# Audio.net
KiCad netlist of a schematic drawn in Altium Designer
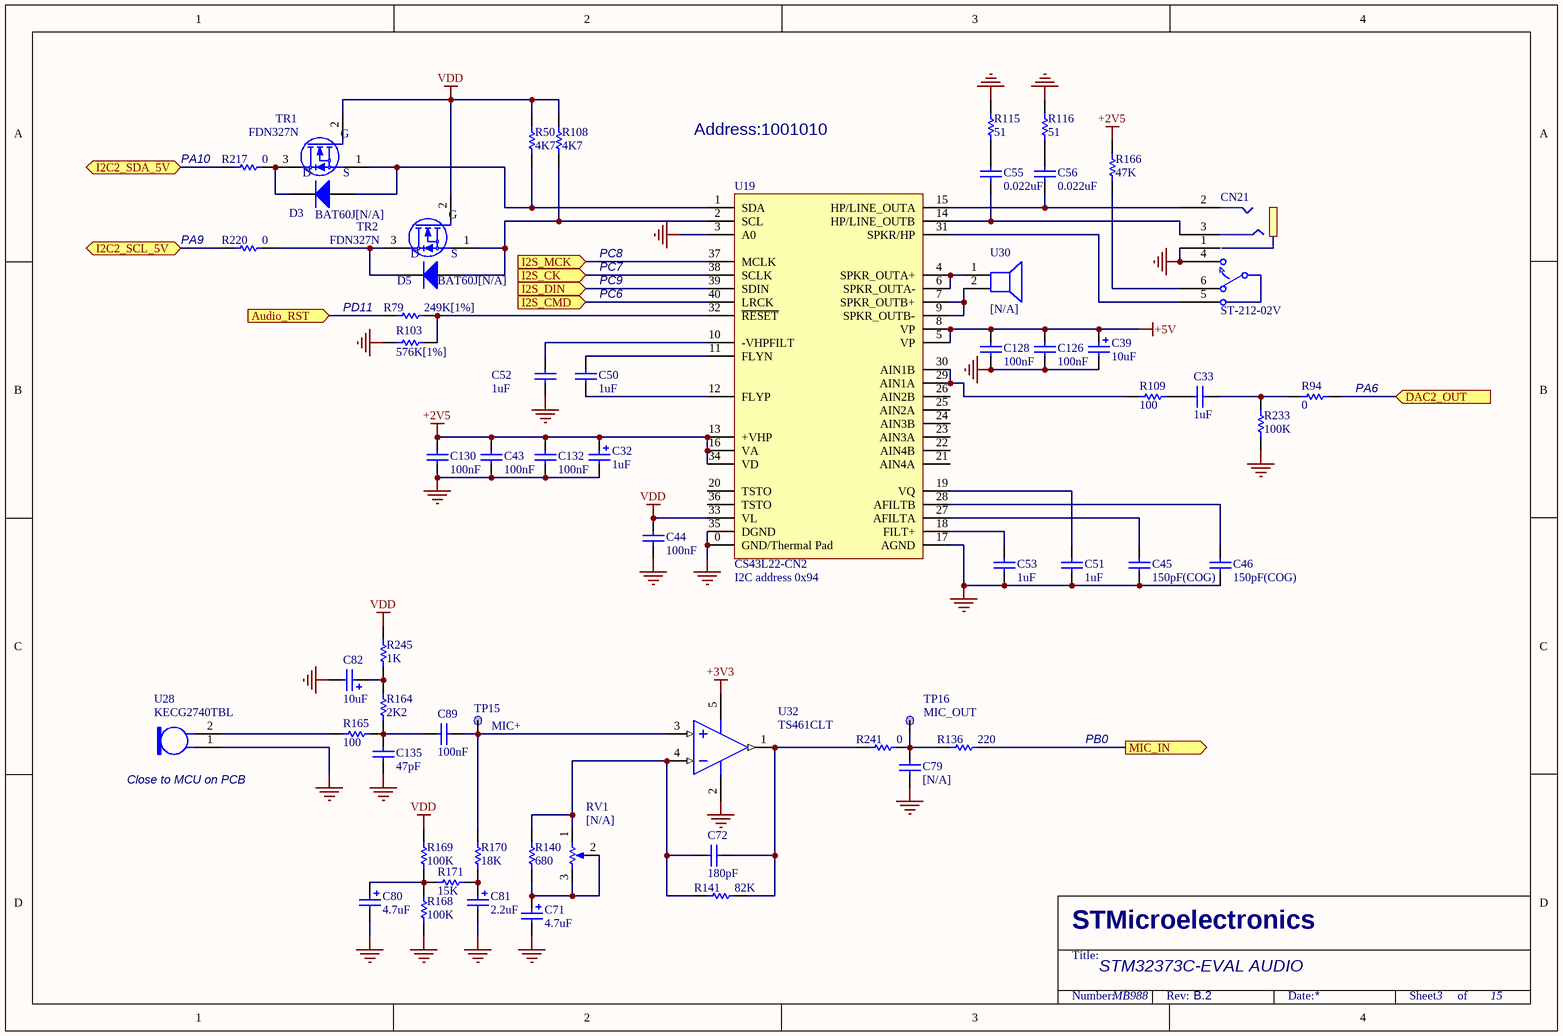
[diagram p0: Audio.SchDoc]

(export (version "E")
  (design (tool "Eeschema 10.0.6"))
  (components
    (comp (ref "C32")
      (value "1uF")
      (footprint "TAN-A")
      (description "Polarized Capacitor (Radial)")
      (fields (field (name "PUBLISHER") "Altium Limited"))
      (libsource (lib "Miscellaneous Devices") (part "Cap Pol1"))
    )
    (comp (ref "C33")
      (value "1uF")
      (footprint "0603C")
      (description "Capacitor")
      (fields (field (name "PUBLISHER") "Altium Limited"))
      (libsource (lib "Miscellaneous Devices") (part "CAP"))
    )
    (comp (ref "C39")
      (value "10uF")
      (footprint "TAN-A")
      (description "Polarized Capacitor (Radial)")
      (fields (field (name "PUBLISHER") "Altium Limited"))
      (libsource (lib "Miscellaneous Devices") (part "Cap Pol1"))
    )
    (comp (ref "C43")
      (value "100nF")
      (footprint "0603C")
      (description "Capacitor")
      (fields (field (name "PUBLISHER") "Altium Limited"))
      (libsource (lib "Miscellaneous Devices") (part "Cap"))
    )
    (comp (ref "C44")
      (value "100nF")
      (footprint "0603C")
      (description "Capacitor")
      (fields (field (name "PUBLISHER") "Altium Limited"))
      (libsource (lib "Miscellaneous Devices") (part "Cap"))
    )
    (comp (ref "C45")
      (value "150pF(COG)")
      (footprint "0603C")
      (description "Capacitor")
      (fields (field (name "PUBLISHER") "Altium Limited"))
      (libsource (lib "Miscellaneous Devices") (part "CAP"))
    )
    (comp (ref "C46")
      (value "150pF(COG)")
      (footprint "0603C")
      (description "Capacitor")
      (fields (field (name "PUBLISHER") "Altium Limited"))
      (libsource (lib "Miscellaneous Devices") (part "CAP"))
    )
    (comp (ref "C50")
      (value "1uF")
      (footprint "0603C")
      (description "Capacitor")
      (fields (field (name "PUBLISHER") "Altium Limited"))
      (libsource (lib "Miscellaneous Devices") (part "CAP"))
    )
    (comp (ref "C51")
      (value "1uF")
      (footprint "0603C")
      (description "Capacitor")
      (fields (field (name "PUBLISHER") "Altium Limited"))
      (libsource (lib "Miscellaneous Devices") (part "CAP"))
    )
    (comp (ref "C52")
      (value "1uF")
      (footprint "0603C")
      (description "Capacitor")
      (fields (field (name "PUBLISHER") "Altium Limited"))
      (libsource (lib "Miscellaneous Devices") (part "CAP"))
    )
    (comp (ref "C53")
      (value "1uF")
      (footprint "0603C")
      (description "Capacitor")
      (fields (field (name "PUBLISHER") "Altium Limited"))
      (libsource (lib "Miscellaneous Devices") (part "CAP"))
    )
    (comp (ref "C55")
      (value "0.022uF")
      (footprint "0603C")
      (description "Capacitor")
      (fields (field (name "PUBLISHER") "Altium Limited"))
      (libsource (lib "Miscellaneous Devices") (part "CAP"))
    )
    (comp (ref "C56")
      (value "0.022uF")
      (footprint "0603C")
      (description "Capacitor")
      (fields (field (name "PUBLISHER") "Altium Limited"))
      (libsource (lib "Miscellaneous Devices") (part "CAP"))
    )
    (comp (ref "C71")
      (value "4.7uF")
      (footprint "TAN-A")
      (description "Polarized Capacitor (Radial)")
      (fields (field (name "PUBLISHER") "Altium Limited"))
      (libsource (lib "*") (part "Cap Pol1"))
    )
    (comp (ref "C72")
      (value "180pF")
      (footprint "0603C")
      (description "Capacitor")
      (fields (field (name "PUBLISHER") "Altium Limited"))
      (libsource (lib "Miscellaneous Devices") (part "CAP"))
    )
    (comp (ref "C79")
      (value "[N/A]")
      (footprint "0603C")
      (description "Capacitor")
      (fields (field (name "PUBLISHER") "Altium Limited"))
      (libsource (lib "Miscellaneous Devices") (part "CAP"))
    )
    (comp (ref "C80")
      (value "4.7uF")
      (footprint "TAN-A")
      (description "Polarized Capacitor (Radial)")
      (fields (field (name "PUBLISHER") "Altium Limited"))
      (libsource (lib "*") (part "Cap Pol1"))
    )
    (comp (ref "C81")
      (value "2.2uF")
      (footprint "0805C")
      (description "Polarized Capacitor (Radial)")
      (fields (field (name "PUBLISHER") "Altium Limited"))
      (libsource (lib "*") (part "Cap Pol1"))
    )
    (comp (ref "C82")
      (value "10uF")
      (footprint "TAN-A")
      (description "Polarized Capacitor (Radial)")
      (fields (field (name "PUBLISHER") "Altium Limited"))
      (libsource (lib "*") (part "Cap Pol1"))
    )
    (comp (ref "C89")
      (value "100nF")
      (footprint "0603C")
      (description "Capacitor")
      (fields (field (name "PUBLISHER") "Altium Limited"))
      (libsource (lib "Miscellaneous Devices") (part "CAP"))
    )
    (comp (ref "C126")
      (value "100nF")
      (footprint "0603C")
      (description "Capacitor")
      (fields (field (name "PUBLISHER") "Altium Limited"))
      (libsource (lib "Miscellaneous Devices") (part "Cap"))
    )
    (comp (ref "C128")
      (value "100nF")
      (footprint "0603C")
      (description "Capacitor")
      (fields (field (name "PUBLISHER") "Altium Limited"))
      (libsource (lib "Miscellaneous Devices") (part "Cap"))
    )
    (comp (ref "C130")
      (value "100nF")
      (footprint "0603C")
      (description "Capacitor")
      (fields (field (name "PUBLISHER") "Altium Limited"))
      (libsource (lib "Miscellaneous Devices") (part "Cap"))
    )
    (comp (ref "C132")
      (value "100nF")
      (footprint "0603C")
      (description "Capacitor")
      (fields (field (name "PUBLISHER") "Altium Limited"))
      (libsource (lib "Miscellaneous Devices") (part "Cap"))
    )
    (comp (ref "C135")
      (value "47pF")
      (footprint "0603C")
      (description "Capacitor")
      (fields (field (name "PUBLISHER") "Altium Limited"))
      (libsource (lib "Miscellaneous Devices") (part "CAP"))
    )
    (comp (ref "CN21")
      (value "ST-212-02V")
      (footprint "ST-212-02V")
      (libsource (lib "MB784") (part "ST-212-02V"))
    )
    (comp (ref "D3")
      (value "BAT60J[N/A]")
      (footprint "SOD-323")
      (description "Default Diode")
      (fields (field (name "PUBLISHER") "Altium Limited"))
      (libsource (lib "Miscellaneous Devices") (part "Diode"))
    )
    (comp (ref "D5")
      (value "BAT60J[N/A]")
      (footprint "SOD-323")
      (description "Default Diode")
      (fields (field (name "PUBLISHER") "Altium Limited"))
      (libsource (lib "Miscellaneous Devices") (part "Diode"))
    )
    (comp (ref "R50")
      (value "4K7")
      (footprint "0603R")
      (description "Resistor")
      (fields (field (name "PUBLISHER") "Altium Limited"))
      (libsource (lib "Miscellaneous Devices") (part "Res1"))
    )
    (comp (ref "R79")
      (value "249K[1%]")
      (footprint "0603R")
      (description "Resistor")
      (fields (field (name "PUBLISHER") "Altium Limited"))
      (libsource (lib "Miscellaneous Devices") (part "res1"))
    )
    (comp (ref "R94")
      (value "0")
      (footprint "0603R")
      (description "Resistor")
      (fields (field (name "PUBLISHER") "Altium Limited"))
      (libsource (lib "Miscellaneous Devices") (part "res1"))
    )
    (comp (ref "R103")
      (value "576K[1%]")
      (footprint "0603R")
      (description "Resistor")
      (fields (field (name "PUBLISHER") "Altium Limited"))
      (libsource (lib "Miscellaneous Devices") (part "res1"))
    )
    (comp (ref "R108")
      (value "4K7")
      (footprint "0603R")
      (description "Resistor")
      (fields (field (name "PUBLISHER") "Altium Limited"))
      (libsource (lib "Miscellaneous Devices") (part "Res1"))
    )
    (comp (ref "R109")
      (value "100")
      (footprint "0603R")
      (description "Resistor")
      (fields (field (name "PUBLISHER") "Altium Limited"))
      (libsource (lib "Miscellaneous Devices") (part "res1"))
    )
    (comp (ref "R115")
      (value "51")
      (footprint "0603R")
      (description "Resistor")
      (fields (field (name "PUBLISHER") "Altium Limited"))
      (libsource (lib "Miscellaneous Devices") (part "res1"))
    )
    (comp (ref "R116")
      (value "51")
      (footprint "0603R")
      (description "Resistor")
      (fields (field (name "PUBLISHER") "Altium Limited"))
      (libsource (lib "Miscellaneous Devices") (part "res1"))
    )
    (comp (ref "R136")
      (value "220")
      (footprint "0603R")
      (description "Resistor")
      (fields (field (name "PUBLISHER") "Altium Limited"))
      (libsource (lib "Miscellaneous Devices") (part "Res1"))
    )
    (comp (ref "R140")
      (value "680")
      (footprint "0603R")
      (description "Resistor")
      (fields (field (name "PUBLISHER") "Altium Limited"))
      (libsource (lib "Miscellaneous Devices") (part "Res1"))
    )
    (comp (ref "R141")
      (value "82K")
      (footprint "0603R")
      (description "Resistor")
      (fields (field (name "PUBLISHER") "Altium Limited"))
      (libsource (lib "Miscellaneous Devices") (part "Res1"))
    )
    (comp (ref "R164")
      (value "2K2")
      (footprint "0603R")
      (description "Resistor")
      (fields (field (name "PUBLISHER") "Altium Limited"))
      (libsource (lib "Miscellaneous Devices") (part "Res1"))
    )
    (comp (ref "R165")
      (value "100")
      (footprint "0603R")
      (description "Resistor")
      (fields (field (name "PUBLISHER") "Altium Limited"))
      (libsource (lib "Miscellaneous Devices") (part "Res1"))
    )
    (comp (ref "R166")
      (value "47K")
      (footprint "0603R")
      (description "Resistor")
      (fields (field (name "PUBLISHER") "Altium Limited"))
      (libsource (lib "Miscellaneous Devices") (part "res1"))
    )
    (comp (ref "R168")
      (value "100K")
      (footprint "0603R")
      (description "Resistor")
      (fields (field (name "PUBLISHER") "Altium Limited"))
      (libsource (lib "Miscellaneous Devices") (part "Res1"))
    )
    (comp (ref "R169")
      (value "100K")
      (footprint "0603R")
      (description "Resistor")
      (fields (field (name "PUBLISHER") "Altium Limited"))
      (libsource (lib "Miscellaneous Devices") (part "Res1"))
    )
    (comp (ref "R170")
      (value "18K")
      (footprint "0603R")
      (description "Resistor")
      (fields (field (name "PUBLISHER") "Altium Limited"))
      (libsource (lib "Miscellaneous Devices") (part "Res1"))
    )
    (comp (ref "R171")
      (value "15K")
      (footprint "0603R")
      (description "Resistor")
      (fields (field (name "PUBLISHER") "Altium Limited"))
      (libsource (lib "Miscellaneous Devices") (part "Res1"))
    )
    (comp (ref "R217")
      (value "0")
      (footprint "0603R")
      (description "Resistor")
      (fields (field (name "PUBLISHER") "Altium Limited"))
      (libsource (lib "Miscellaneous Devices") (part "Res1"))
    )
    (comp (ref "R220")
      (value "0")
      (footprint "0603R")
      (description "Resistor")
      (fields (field (name "PUBLISHER") "Altium Limited"))
      (libsource (lib "Miscellaneous Devices") (part "Res1"))
    )
    (comp (ref "R233")
      (value "100K")
      (footprint "0603R")
      (description "Resistor")
      (fields (field (name "PUBLISHER") "Altium Limited"))
      (libsource (lib "Miscellaneous Devices") (part "res1"))
    )
    (comp (ref "R241")
      (value "0")
      (footprint "0603R")
      (description "Resistor")
      (fields (field (name "PUBLISHER") "Altium Limited"))
      (libsource (lib "Miscellaneous Devices") (part "Res1"))
    )
    (comp (ref "R245")
      (value "1K")
      (footprint "0603R")
      (description "Resistor")
      (fields (field (name "PUBLISHER") "Altium Limited"))
      (libsource (lib "Miscellaneous Devices") (part "Res1"))
    )
    (comp (ref "RV1") (value "[N/A]") (footprint "3314-J") (libsource (lib "STR910_SCHLIB") (part "RV")))
    (comp (ref "TP15") (value "MIC+") (footprint "TP") (libsource (lib "*") (part "TP")))
    (comp (ref "TP16") (value "MIC_OUT") (footprint "TP") (libsource (lib "*") (part "TP")))
    (comp (ref "TR1") (value "FDN327N") (footprint "SOT-23") (libsource (lib "MB525") (part "2N7000")))
    (comp (ref "TR2") (value "FDN327N") (footprint "SOT-23") (libsource (lib "MB525") (part "2N7000")))
    (comp (ref "U19")
      (value "CS43L22-CN2")
      (footprint "QFN40(6*6)")
      (libsource (lib "MB784") (part "CS43L22"))
    )
    (comp (ref "U28")
      (value "KECG2740TBL")
      (footprint "KEC2740")
      (description "Microphone")
      (fields (field (name "PUBLISHER") "Altium Limited"))
      (libsource (lib "Miscellaneous Devices") (part "Mic2"))
    )
    (comp (ref "U30")
      (value "[N/A]")
      (footprint "KS1708")
      (description "Loudspeaker")
      (fields (field (name "PUBLISHER") "Altium Limited"))
      (libsource (lib "Miscellaneous Devices") (part "Speaker"))
    )
    (comp (ref "U32")
      (value "TS461CLT")
      (footprint "SOT-23-5L")
      (libsource (lib "MB819_1") (part "TS461CLT"))
    )
  )
  (nets
    (net (code "1") (name "+2V5") (class "Default")
      (node (ref "C130") (pin "1") (pinfunction "1_1") (pintype "passive"))
      (node (ref "C132") (pin "1") (pinfunction "1_1") (pintype "passive"))
      (node (ref "C32") (pin "1") (pinfunction "1_1") (pintype "passive"))
      (node (ref "C43") (pin "1") (pinfunction "1_1") (pintype "passive"))
      (node (ref "R166") (pin "1") (pinfunction "1_1") (pintype "passive"))
      (node (ref "U19") (pin "13") (pinfunction "+VHP_13") (pintype "passive"))
      (node (ref "U19") (pin "16") (pinfunction "VA_16") (pintype "passive"))
      (node (ref "U19") (pin "34") (pinfunction "VD_34") (pintype "passive"))
    )
    (net (code "2") (name "+3V3") (class "Default")
      (node (ref "U32") (pin "5") (pinfunction "VCC_5") (pintype "power_in"))
    )
    (net (code "3") (name "+5V") (class "Default")
      (node (ref "C126") (pin "1") (pinfunction "1_1") (pintype "passive"))
      (node (ref "C128") (pin "1") (pinfunction "1_1") (pintype "passive"))
      (node (ref "C39") (pin "1") (pinfunction "1_1") (pintype "passive"))
      (node (ref "U19") (pin "5") (pinfunction "VP_5") (pintype "passive"))
      (node (ref "U19") (pin "8") (pinfunction "VP_8") (pintype "passive"))
    )
    (net (code "4") (name "/Audio_RST") (class "Default")
      (node (ref "R79") (pin "2") (pinfunction "2_2") (pintype "passive"))
    )
    (net (code "5") (name "/DAC2_OUT") (class "Default")
      (node (ref "R94") (pin "2") (pinfunction "2_2") (pintype "passive"))
    )
    (net (code "6") (name "/I2C2_SCL_5V") (class "Default")
      (node (ref "R220") (pin "1") (pinfunction "1_1") (pintype "passive"))
    )
    (net (code "7") (name "/I2C2_SDA_5V") (class "Default")
      (node (ref "R217") (pin "1") (pinfunction "1_1") (pintype "passive"))
    )
    (net (code "8") (name "/I2S_CK") (class "Default")
      (node (ref "U19") (pin "38") (pinfunction "SCLK_38") (pintype "passive"))
    )
    (net (code "9") (name "/I2S_CMD") (class "Default")
      (node (ref "U19") (pin "40") (pinfunction "LRCK_40") (pintype "passive"))
    )
    (net (code "10") (name "/I2S_DIN") (class "Default")
      (node (ref "U19") (pin "39") (pinfunction "SDIN_39") (pintype "passive"))
    )
    (net (code "11") (name "/I2S_MCK") (class "Default")
      (node (ref "U19") (pin "37") (pinfunction "MCLK_37") (pintype "passive"))
    )
    (net (code "12") (name "/MIC_IN") (class "Default")
      (node (ref "R136") (pin "1") (pinfunction "1_1") (pintype "passive"))
    )
    (net (code "13") (name "GND") (class "Default")
      (node (ref "C126") (pin "2") (pinfunction "2_2") (pintype "passive"))
      (node (ref "C128") (pin "2") (pinfunction "2_2") (pintype "passive"))
      (node (ref "C130") (pin "2") (pinfunction "2_2") (pintype "passive"))
      (node (ref "C132") (pin "2") (pinfunction "2_2") (pintype "passive"))
      (node (ref "C135") (pin "2") (pinfunction "2_2") (pintype "passive"))
      (node (ref "C32") (pin "2") (pinfunction "2_2") (pintype "passive"))
      (node (ref "C39") (pin "2") (pinfunction "2_2") (pintype "passive"))
      (node (ref "C43") (pin "2") (pinfunction "2_2") (pintype "passive"))
      (node (ref "C44") (pin "2") (pinfunction "2_2") (pintype "passive"))
      (node (ref "C45") (pin "1") (pinfunction "1_1") (pintype "passive"))
      (node (ref "C46") (pin "1") (pinfunction "1_1") (pintype "passive"))
      (node (ref "C51") (pin "1") (pinfunction "1_1") (pintype "passive"))
      (node (ref "C52") (pin "2") (pinfunction "2_2") (pintype "passive"))
      (node (ref "C53") (pin "1") (pinfunction "1_1") (pintype "passive"))
      (node (ref "C71") (pin "2") (pinfunction "2_2") (pintype "passive"))
      (node (ref "C79") (pin "2") (pinfunction "2_2") (pintype "passive"))
      (node (ref "C80") (pin "2") (pinfunction "2_2") (pintype "passive"))
      (node (ref "C81") (pin "2") (pinfunction "2_2") (pintype "passive"))
      (node (ref "C82") (pin "2") (pinfunction "2_2") (pintype "passive"))
      (node (ref "CN21") (pin "1") (pintype "passive"))
      (node (ref "CN21") (pin "4") (pintype "passive"))
      (node (ref "R103") (pin "1") (pinfunction "1_1") (pintype "passive"))
      (node (ref "R115") (pin "1") (pinfunction "1_1") (pintype "passive"))
      (node (ref "R116") (pin "1") (pinfunction "1_1") (pintype "passive"))
      (node (ref "R168") (pin "2") (pinfunction "2_2") (pintype "passive"))
      (node (ref "R233") (pin "2") (pinfunction "2_2") (pintype "passive"))
      (node (ref "U19") (pin "0") (pinfunction "GND/Thermal_Pad_0") (pintype "passive"))
      (node (ref "U19") (pin "17") (pinfunction "AGND_17") (pintype "passive"))
      (node (ref "U19") (pin "3") (pinfunction "A0_3") (pintype "passive"))
      (node (ref "U19") (pin "35") (pinfunction "DGND_35") (pintype "passive"))
      (node (ref "U28") (pin "1") (pinfunction "1_1") (pintype "passive"))
      (node (ref "U32") (pin "2") (pinfunction "VDD_2") (pintype "power_in"))
    )
    (net (code "14") (name "Net-(C33-Pad1)") (class "Default")
      (node (ref "C33") (pin "1") (pinfunction "1_1") (pintype "passive"))
      (node (ref "R109") (pin "1") (pinfunction "1_1") (pintype "passive"))
    )
    (net (code "15") (name "Net-(C33-Pad2)") (class "Default")
      (node (ref "C33") (pin "2") (pinfunction "2_2") (pintype "passive"))
      (node (ref "R233") (pin "1") (pinfunction "1_1") (pintype "passive"))
      (node (ref "R94") (pin "1") (pinfunction "1_1") (pintype "passive"))
    )
    (net (code "16") (name "Net-(C55-Pad1)") (class "Default")
      (node (ref "C55") (pin "1") (pinfunction "1_1") (pintype "passive"))
      (node (ref "R115") (pin "2") (pinfunction "2_2") (pintype "passive"))
    )
    (net (code "17") (name "Net-(C56-Pad1)") (class "Default")
      (node (ref "C56") (pin "1") (pinfunction "1_1") (pintype "passive"))
      (node (ref "R116") (pin "2") (pinfunction "2_2") (pintype "passive"))
    )
    (net (code "18") (name "Net-(C79-Pad1)") (class "Default")
      (node (ref "C79") (pin "1") (pinfunction "1_1") (pintype "passive"))
      (node (ref "R136") (pin "2") (pinfunction "2_2") (pintype "passive"))
      (node (ref "R241") (pin "1") (pinfunction "1_1") (pintype "passive"))
      (node (ref "TP16") (pin "1") (pinfunction "1_1") (pintype "passive"))
    )
    (net (code "19") (name "Net-(C80-Pad1)") (class "Default")
      (node (ref "C80") (pin "1") (pinfunction "1_1") (pintype "passive"))
      (node (ref "R168") (pin "1") (pinfunction "1_1") (pintype "passive"))
      (node (ref "R169") (pin "2") (pinfunction "2_2") (pintype "passive"))
      (node (ref "R171") (pin "1") (pinfunction "1_1") (pintype "passive"))
    )
    (net (code "20") (name "Net-(C81-Pad1)") (class "Default")
      (node (ref "C81") (pin "1") (pinfunction "1_1") (pintype "passive"))
      (node (ref "R170") (pin "1") (pinfunction "1_1") (pintype "passive"))
      (node (ref "R171") (pin "2") (pinfunction "2_2") (pintype "passive"))
    )
    (net (code "21") (name "Net-(C82-Pad1)") (class "Default")
      (node (ref "C82") (pin "1") (pinfunction "1_1") (pintype "passive"))
      (node (ref "R164") (pin "2") (pinfunction "2_2") (pintype "passive"))
      (node (ref "R245") (pin "1") (pinfunction "1_1") (pintype "passive"))
    )
    (net (code "22") (name "Net-(C135-Pad1)") (class "Default")
      (node (ref "C135") (pin "1") (pinfunction "1_1") (pintype "passive"))
      (node (ref "C89") (pin "1") (pinfunction "1_1") (pintype "passive"))
      (node (ref "R164") (pin "1") (pinfunction "1_1") (pintype "passive"))
      (node (ref "R165") (pin "1") (pinfunction "1_1") (pintype "passive"))
    )
    (net (code "23") (name "Net-(CN21-Pad6)") (class "Default")
      (node (ref "CN21") (pin "6") (pintype "passive"))
      (node (ref "R166") (pin "2") (pinfunction "2_2") (pintype "passive"))
    )
    (net (code "24") (name "Net-(D3-A)") (class "Default")
      (node (ref "D3") (pin "1") (pinfunction "A_1") (pintype "passive"))
      (node (ref "R50") (pin "1") (pinfunction "1_1") (pintype "passive"))
      (node (ref "TR1") (pin "1") (pinfunction "S_1") (pintype "passive"))
      (node (ref "U19") (pin "1") (pinfunction "SDA_1") (pintype "passive"))
    )
    (net (code "25") (name "Net-(D3-K)") (class "Default")
      (node (ref "D3") (pin "2") (pinfunction "K_2") (pintype "passive"))
      (node (ref "R217") (pin "2") (pinfunction "2_2") (pintype "passive"))
      (node (ref "TR1") (pin "3") (pinfunction "D_3") (pintype "passive"))
    )
    (net (code "26") (name "Net-(D5-A)") (class "Default")
      (node (ref "D5") (pin "1") (pinfunction "A_1") (pintype "passive"))
      (node (ref "R108") (pin "1") (pinfunction "1_1") (pintype "passive"))
      (node (ref "TR2") (pin "1") (pinfunction "S_1") (pintype "passive"))
      (node (ref "U19") (pin "2") (pinfunction "SCL_2") (pintype "passive"))
    )
    (net (code "27") (name "Net-(D5-K)") (class "Default")
      (node (ref "D5") (pin "2") (pinfunction "K_2") (pintype "passive"))
      (node (ref "R220") (pin "2") (pinfunction "2_2") (pintype "passive"))
      (node (ref "TR2") (pin "3") (pinfunction "D_3") (pintype "passive"))
    )
    (net (code "28") (name "Net-(R165-Pad2)") (class "Default")
      (node (ref "R165") (pin "2") (pinfunction "2_2") (pintype "passive"))
      (node (ref "U28") (pin "2") (pinfunction "2_2") (pintype "passive"))
    )
    (net (code "29") (name "Net-(RV1-BOT)") (class "Default")
      (node (ref "C72") (pin "1") (pinfunction "1_1") (pintype "passive"))
      (node (ref "R140") (pin "1") (pinfunction "1_1") (pintype "passive"))
      (node (ref "R141") (pin "2") (pinfunction "2_2") (pintype "passive"))
      (node (ref "RV1") (pin "1") (pinfunction "BOT_1") (pintype "passive"))
      (node (ref "U32") (pin "4") (pinfunction "IN-_4") (pintype "input"))
    )
    (net (code "30") (name "Net-(RV1-TAP)") (class "Default")
      (node (ref "C71") (pin "1") (pinfunction "1_1") (pintype "passive"))
      (node (ref "R140") (pin "2") (pinfunction "2_2") (pintype "passive"))
      (node (ref "RV1") (pin "2") (pinfunction "TAP_2") (pintype "passive"))
      (node (ref "RV1") (pin "3") (pinfunction "TOP_3") (pintype "passive"))
    )
    (net (code "31") (name "Net-(U19--VHPFILT)") (class "Default")
      (node (ref "C52") (pin "1") (pinfunction "1_1") (pintype "passive"))
      (node (ref "U19") (pin "10") (pinfunction "-VHPFILT_10") (pintype "passive"))
    )
    (net (code "32") (name "Net-(U19-AFILTA)") (class "Default")
      (node (ref "C45") (pin "2") (pinfunction "2_2") (pintype "passive"))
      (node (ref "U19") (pin "27") (pinfunction "AFILTA_27") (pintype "passive"))
    )
    (net (code "33") (name "Net-(U19-AFILTB)") (class "Default")
      (node (ref "C46") (pin "2") (pinfunction "2_2") (pintype "passive"))
      (node (ref "U19") (pin "28") (pinfunction "AFILTB_28") (pintype "passive"))
    )
    (net (code "34") (name "Net-(U19-AIN1A)") (class "Default")
      (node (ref "R109") (pin "2") (pinfunction "2_2") (pintype "passive"))
      (node (ref "U19") (pin "29") (pinfunction "AIN1A_29") (pintype "passive"))
      (node (ref "U19") (pin "30") (pinfunction "AIN1B_30") (pintype "passive"))
    )
    (net (code "35") (name "Net-(U19-FILT+)") (class "Default")
      (node (ref "C53") (pin "2") (pinfunction "2_2") (pintype "passive"))
      (node (ref "U19") (pin "18") (pinfunction "FILT+_18") (pintype "passive"))
    )
    (net (code "36") (name "Net-(U19-FLYN)") (class "Default")
      (node (ref "C50") (pin "2") (pinfunction "2_2") (pintype "passive"))
      (node (ref "U19") (pin "11") (pinfunction "FLYN_11") (pintype "passive"))
    )
    (net (code "37") (name "Net-(U19-FLYP)") (class "Default")
      (node (ref "C50") (pin "1") (pinfunction "1_1") (pintype "passive"))
      (node (ref "U19") (pin "12") (pinfunction "FLYP_12") (pintype "passive"))
    )
    (net (code "38") (name "Net-(U19-HP{slash}LINE_OUTA)") (class "Default")
      (node (ref "C56") (pin "2") (pinfunction "2_2") (pintype "passive"))
      (node (ref "CN21") (pin "2") (pintype "passive"))
      (node (ref "U19") (pin "15") (pinfunction "HP/LINE_OUTA_15") (pintype "passive"))
    )
    (net (code "39") (name "Net-(U19-HP{slash}LINE_OUTB)") (class "Default")
      (node (ref "C55") (pin "2") (pinfunction "2_2") (pintype "passive"))
      (node (ref "CN21") (pin "3") (pintype "passive"))
      (node (ref "U19") (pin "14") (pinfunction "HP/LINE_OUTB_14") (pintype "passive"))
    )
    (net (code "40") (name "Net-(U19-SPKR_OUTA+)") (class "Default")
      (node (ref "U19") (pin "4") (pinfunction "SPKR_OUTA+_4") (pintype "passive"))
      (node (ref "U19") (pin "6") (pinfunction "SPKR_OUTA-_6") (pintype "passive"))
      (node (ref "U30") (pin "1") (pinfunction "+_1") (pintype "passive"))
    )
    (net (code "41") (name "Net-(U19-SPKR_OUTB+)") (class "Default")
      (node (ref "U19") (pin "7") (pinfunction "SPKR_OUTB+_7") (pintype "passive"))
      (node (ref "U19") (pin "9") (pinfunction "SPKR_OUTB-_9") (pintype "passive"))
      (node (ref "U30") (pin "2") (pinfunction "-_2") (pintype "passive"))
    )
    (net (code "42") (name "Net-(U19-SPKR{slash}HP)") (class "Default")
      (node (ref "CN21") (pin "5") (pintype "passive"))
      (node (ref "U19") (pin "31") (pinfunction "SPKR/HP_31") (pintype "passive"))
    )
    (net (code "43") (name "Net-(U19-VQ)") (class "Default")
      (node (ref "C51") (pin "2") (pinfunction "2_2") (pintype "passive"))
      (node (ref "U19") (pin "19") (pinfunction "VQ_19") (pintype "passive"))
    )
    (net (code "44") (name "Net-(U19-~{RESET})") (class "Default")
      (node (ref "R103") (pin "2") (pinfunction "2_2") (pintype "passive"))
      (node (ref "R79") (pin "1") (pinfunction "1_1") (pintype "passive"))
      (node (ref "U19") (pin "32") (pinfunction "~{RESET}_32") (pintype "passive"))
    )
    (net (code "45") (name "Net-(U32-IN+)") (class "Default")
      (node (ref "C89") (pin "2") (pinfunction "2_2") (pintype "passive"))
      (node (ref "R170") (pin "2") (pinfunction "2_2") (pintype "passive"))
      (node (ref "TP15") (pin "1") (pinfunction "1_1") (pintype "passive"))
      (node (ref "U32") (pin "3") (pinfunction "IN+_3") (pintype "input"))
    )
    (net (code "46") (name "Net-(U32-OUT)") (class "Default")
      (node (ref "C72") (pin "2") (pinfunction "2_2") (pintype "passive"))
      (node (ref "R141") (pin "1") (pinfunction "1_1") (pintype "passive"))
      (node (ref "R241") (pin "2") (pinfunction "2_2") (pintype "passive"))
      (node (ref "U32") (pin "1") (pinfunction "OUT_1") (pintype "output"))
    )
    (net (code "47") (name "VDD") (class "Default")
      (node (ref "C44") (pin "1") (pinfunction "1_1") (pintype "passive"))
      (node (ref "R108") (pin "2") (pinfunction "2_2") (pintype "passive"))
      (node (ref "R169") (pin "1") (pinfunction "1_1") (pintype "passive"))
      (node (ref "R245") (pin "2") (pinfunction "2_2") (pintype "passive"))
      (node (ref "R50") (pin "2") (pinfunction "2_2") (pintype "passive"))
      (node (ref "TR1") (pin "2") (pinfunction "G_2") (pintype "passive"))
      (node (ref "TR2") (pin "2") (pinfunction "G_2") (pintype "passive"))
      (node (ref "U19") (pin "33") (pinfunction "VL_33") (pintype "passive"))
    )
    (net (code "48") (name "unconnected-(U19-AIN2A-Pad25)") (class "Default")
      (node (ref "U19") (pin "25") (pinfunction "AIN2A_25") (pintype "passive"))
    )
    (net (code "49") (name "unconnected-(U19-AIN2B-Pad26)") (class "Default")
      (node (ref "U19") (pin "26") (pinfunction "AIN2B_26") (pintype "passive"))
    )
    (net (code "50") (name "unconnected-(U19-AIN3A-Pad23)") (class "Default")
      (node (ref "U19") (pin "23") (pinfunction "AIN3A_23") (pintype "passive"))
    )
    (net (code "51") (name "unconnected-(U19-AIN3B-Pad24)") (class "Default")
      (node (ref "U19") (pin "24") (pinfunction "AIN3B_24") (pintype "passive"))
    )
    (net (code "52") (name "unconnected-(U19-AIN4A-Pad21)") (class "Default")
      (node (ref "U19") (pin "21") (pinfunction "AIN4A_21") (pintype "passive"))
    )
    (net (code "53") (name "unconnected-(U19-AIN4B-Pad22)") (class "Default")
      (node (ref "U19") (pin "22") (pinfunction "AIN4B_22") (pintype "passive"))
    )
    (net (code "54") (name "unconnected-(U19-TSTO-Pad20)") (class "Default")
      (node (ref "U19") (pin "20") (pinfunction "TSTO_20") (pintype "passive"))
    )
    (net (code "55") (name "unconnected-(U19-TSTO-Pad36)") (class "Default")
      (node (ref "U19") (pin "36") (pinfunction "TSTO_36") (pintype "passive"))
    )
  )
)
